# v001.net
KiCad netlist of a schematic drawn in EAGLE
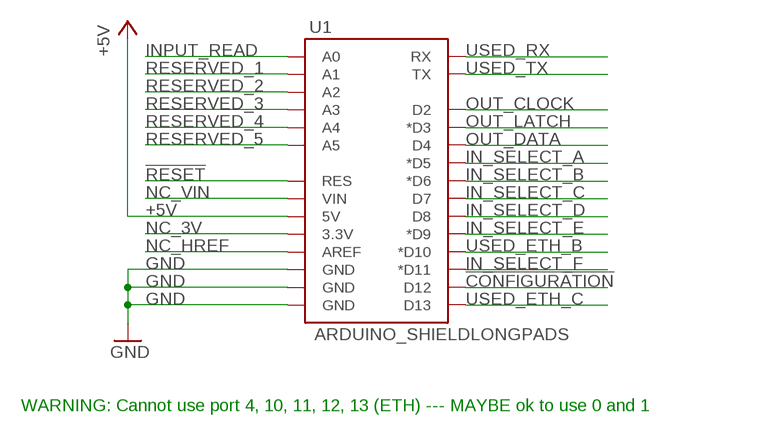
[diagram p0: schematic, sheet 1]
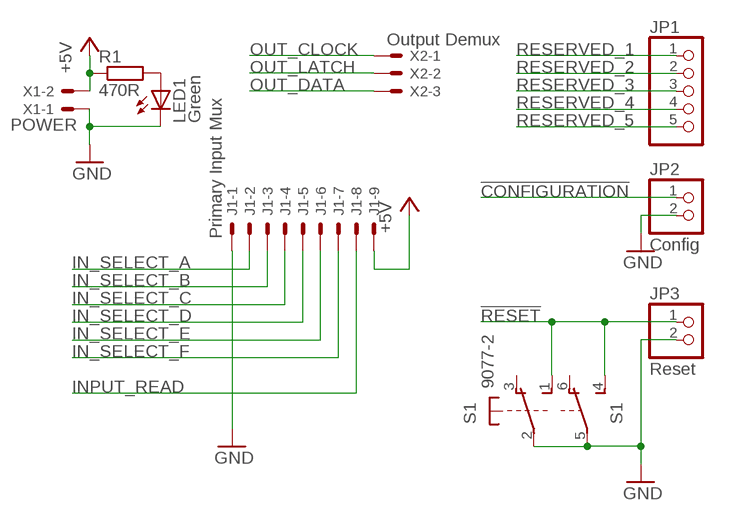
[diagram p1: schematic, sheet 2]

(export (version "E")
  (design (tool "Eeschema 10.0.6"))
  (components
    (comp (ref "J1")
      (value "Primary Input Mux")
      (footprint "eagle-import:6410-09")
      (libsource (lib "eagle-import") (part "22-?-0927-2091"))
    )
    (comp (ref "JP1")
      (value "PINHD-1X5")
      (footprint "eagle-import:1X05")
      (libsource (lib "eagle-import") (part "PINHD-1X5"))
    )
    (comp (ref "JP2")
      (value "Config")
      (footprint "eagle-import:1X02")
      (libsource (lib "eagle-import") (part "PINHD-1X2"))
    )
    (comp (ref "JP3")
      (value "Reset")
      (footprint "eagle-import:1X02")
      (libsource (lib "eagle-import") (part "PINHD-1X2"))
    )
    (comp (ref "LED1")
      (value "Green")
      (footprint "eagle-import:LED3MM")
      (libsource (lib "eagle-import") (part "LED3MM"))
    )
    (comp (ref "R1")
      (value "470R")
      (footprint "eagle-import:0204_7")
      (libsource (lib "eagle-import") (part "R-EU_0204/7"))
    )
    (comp (ref "S1")
      (value "9077-2")
      (footprint "eagle-import:9077-2")
      (libsource (lib "eagle-import") (part "9077-2"))
    )
    (comp (ref "X1")
      (value "POWER")
      (footprint "eagle-import:22-23-2021")
      (fields (field (name "MF") "MOLEX") (field (name "MPN") "22-23-2021"))
      (libsource (lib "eagle-import") (part "22-23-2021"))
    )
    (comp (ref "X2")
      (value "Output Demux")
      (footprint "eagle-import:22-23-2031")
      (fields (field (name "MF") "MOLEX") (field (name "MPN") "22-23-2031"))
      (libsource (lib "eagle-import") (part "22-23-2031"))
    )
    (comp (ref "U1")
      (value "ARDUINO_SHIELDLONGPADS")
      (footprint "eagle-import:DUEMILANOVE_SHIELD_LONGPADS")
      (libsource (lib "eagle-import") (part "ARDUINO_SHIELDLONGPADS"))
    )
  )
  (nets
    (net (code "1") (name "+5V") (class "Default")
      (node (ref "J1") (pin "9") (pinfunction "S_9") (pintype "passive"))
      (node (ref "R1") (pin "1") (pinfunction "1_1") (pintype "passive"))
      (node (ref "U1") (pin "5V") (pinfunction "5V_5V") (pintype "bidirectional"))
      (node (ref "X1") (pin "2") (pinfunction "S_2") (pintype "passive"))
    )
    (net (code "2") (name "GND") (class "Default")
      (node (ref "J1") (pin "1") (pinfunction "S_1") (pintype "passive"))
      (node (ref "JP2") (pin "2") (pinfunction "2_2") (pintype "passive"))
      (node (ref "JP3") (pin "2") (pinfunction "2_2") (pintype "passive"))
      (node (ref "LED1") (pin "K") (pinfunction "C_K") (pintype "passive"))
      (node (ref "S1") (pin "2") (pinfunction "P_2") (pintype "passive"))
      (node (ref "S1") (pin "5") (pinfunction "P_5") (pintype "passive"))
      (node (ref "U1") (pin "GND@0") (pinfunction "GND_GND@0") (pintype "bidirectional"))
      (node (ref "U1") (pin "GND@1") (pinfunction "GND_GND@1") (pintype "bidirectional"))
      (node (ref "U1") (pin "GND@2") (pinfunction "GND_GND@2") (pintype "bidirectional"))
      (node (ref "X1") (pin "1") (pinfunction "S_1") (pintype "passive"))
    )
    (net (code "3") (name "INPUT_READ") (class "Default")
      (node (ref "J1") (pin "8") (pinfunction "S_8") (pintype "passive"))
      (node (ref "U1") (pin "A0") (pinfunction "A0_A0") (pintype "bidirectional"))
    )
    (net (code "4") (name "IN_SELECT_A") (class "Default")
      (node (ref "J1") (pin "2") (pinfunction "S_2") (pintype "passive"))
      (node (ref "U1") (pin "D5") (pinfunction "*D5_D5") (pintype "bidirectional"))
    )
    (net (code "5") (name "IN_SELECT_B") (class "Default")
      (node (ref "J1") (pin "3") (pinfunction "S_3") (pintype "passive"))
      (node (ref "U1") (pin "D6") (pinfunction "*D6_D6") (pintype "bidirectional"))
    )
    (net (code "6") (name "IN_SELECT_C") (class "Default")
      (node (ref "J1") (pin "4") (pinfunction "S_4") (pintype "passive"))
      (node (ref "U1") (pin "D7") (pinfunction "D7_D7") (pintype "bidirectional"))
    )
    (net (code "7") (name "IN_SELECT_D") (class "Default")
      (node (ref "J1") (pin "5") (pinfunction "S_5") (pintype "passive"))
      (node (ref "U1") (pin "D8") (pinfunction "D8_D8") (pintype "bidirectional"))
    )
    (net (code "8") (name "IN_SELECT_E") (class "Default")
      (node (ref "J1") (pin "6") (pinfunction "S_6") (pintype "passive"))
      (node (ref "U1") (pin "D9") (pinfunction "*D9_D9") (pintype "bidirectional"))
    )
    (net (code "9") (name "IN_SELECT_F") (class "Default")
      (node (ref "J1") (pin "7") (pinfunction "S_7") (pintype "passive"))
      (node (ref "U1") (pin "D11") (pinfunction "*D11_D11") (pintype "bidirectional"))
    )
    (net (code "10") (name "NC_3V") (class "Default")
      (node (ref "U1") (pin "3.3V") (pinfunction "3.3V_3.3V") (pintype "bidirectional"))
    )
    (net (code "11") (name "NC_HREF") (class "Default")
      (node (ref "U1") (pin "AREF") (pinfunction "AREF_AREF") (pintype "bidirectional"))
    )
    (net (code "12") (name "NC_VIN") (class "Default")
      (node (ref "U1") (pin "VIN") (pinfunction "VIN_VIN") (pintype "bidirectional"))
    )
    (net (code "13") (name "Net-(LED1-PadA)") (class "Default")
      (node (ref "LED1") (pin "A") (pinfunction "A_A") (pintype "passive"))
      (node (ref "R1") (pin "2") (pinfunction "2_2") (pintype "passive"))
    )
    (net (code "14") (name "OUT_CLOCK") (class "Default")
      (node (ref "U1") (pin "D2") (pinfunction "D2_D2") (pintype "bidirectional"))
      (node (ref "X2") (pin "1") (pinfunction "S_1") (pintype "passive"))
    )
    (net (code "15") (name "OUT_DATA") (class "Default")
      (node (ref "U1") (pin "D4") (pinfunction "D4_D4") (pintype "bidirectional"))
      (node (ref "X2") (pin "3") (pinfunction "S_3") (pintype "passive"))
    )
    (net (code "16") (name "OUT_LATCH") (class "Default")
      (node (ref "U1") (pin "D3") (pinfunction "*D3_D3") (pintype "bidirectional"))
      (node (ref "X2") (pin "2") (pinfunction "S_2") (pintype "passive"))
    )
    (net (code "17") (name "RESERVED_1") (class "Default")
      (node (ref "JP1") (pin "1") (pinfunction "1_1") (pintype "passive"))
      (node (ref "U1") (pin "A1") (pinfunction "A1_A1") (pintype "bidirectional"))
    )
    (net (code "18") (name "RESERVED_2") (class "Default")
      (node (ref "JP1") (pin "2") (pinfunction "2_2") (pintype "passive"))
      (node (ref "U1") (pin "A2") (pinfunction "A2_A2") (pintype "bidirectional"))
    )
    (net (code "19") (name "RESERVED_3") (class "Default")
      (node (ref "JP1") (pin "3") (pinfunction "3_3") (pintype "passive"))
      (node (ref "U1") (pin "A3") (pinfunction "A3_A3") (pintype "bidirectional"))
    )
    (net (code "20") (name "RESERVED_4") (class "Default")
      (node (ref "JP1") (pin "4") (pinfunction "4_4") (pintype "passive"))
      (node (ref "U1") (pin "A4") (pinfunction "A4_A4") (pintype "bidirectional"))
    )
    (net (code "21") (name "RESERVED_5") (class "Default")
      (node (ref "JP1") (pin "5") (pinfunction "5_5") (pintype "passive"))
      (node (ref "U1") (pin "A5") (pinfunction "A5_A5") (pintype "bidirectional"))
    )
    (net (code "22") (name "USED_ETH_B") (class "Default")
      (node (ref "U1") (pin "D10") (pinfunction "*D10_D10") (pintype "bidirectional"))
    )
    (net (code "23") (name "USED_ETH_C") (class "Default")
      (node (ref "U1") (pin "D13") (pinfunction "D13_D13") (pintype "bidirectional"))
    )
    (net (code "24") (name "USED_RX") (class "Default")
      (node (ref "U1") (pin "RX") (pinfunction "RX_RX") (pintype "bidirectional"))
    )
    (net (code "25") (name "USED_TX") (class "Default")
      (node (ref "U1") (pin "TX") (pinfunction "TX_TX") (pintype "bidirectional"))
    )
    (net (code "26") (name "unconnected-(S1A-O-Pad3)") (class "Default")
      (node (ref "S1") (pin "3") (pinfunction "O_3") (pintype "passive"))
    )
    (net (code "27") (name "unconnected-(S1B-O-Pad6)") (class "Default")
      (node (ref "S1") (pin "6") (pinfunction "O_6") (pintype "passive"))
    )
    (net (code "28") (name "~{CONFIGURATION}") (class "Default")
      (node (ref "JP2") (pin "1") (pinfunction "1_1") (pintype "passive"))
      (node (ref "U1") (pin "D12") (pinfunction "D12_D12") (pintype "bidirectional"))
    )
    (net (code "29") (name "~{RESET}") (class "Default")
      (node (ref "JP3") (pin "1") (pinfunction "1_1") (pintype "passive"))
      (node (ref "S1") (pin "1") (pinfunction "S_1") (pintype "passive"))
      (node (ref "S1") (pin "4") (pinfunction "S_4") (pintype "passive"))
      (node (ref "U1") (pin "RES") (pinfunction "RES_RES") (pintype "bidirectional"))
    )
  )
)
